# Placa_de_grava_o.net
KiCad netlist of a schematic drawn in Altium Designer
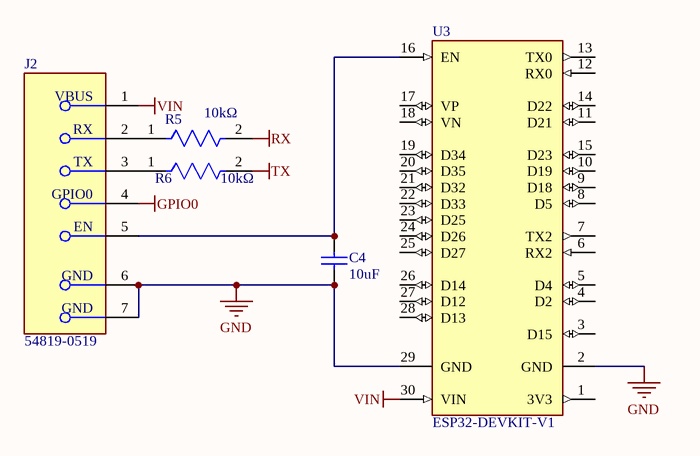
[diagram p0: Placa de gravação.SchDoc]

(export (version "E")
  (design (tool "Eeschema 10.0.6"))
  (components
    (comp (ref "C4")
      (value "10uF")
      (footprint "C_0805")
      (description "Cap Ceramic 1uF 16V X5R 10% SMD 0805 85C Plastic T/R")
      (fields
        (field (name "MANUFACTURER") "KEMET")
        (field (name "MANUFACTURER PART NUMBER") "C0805C105K4PACTU")
      )
      (libsource (lib "uSimar_Components") (part "C0805C105K4PACTU"))
    )
    (comp (ref "J2")
      (value "54819-0519")
      (footprint "FP-54819-0519-MFG")
      (description "CONN RCPT USB2.0 MINI B 5P R/A")
      (libsource (lib "uSimar_Components") (part "CMP-04767-000009-1"))
    )
    (comp (ref "R5")
      (value "10kΩ")
      (footprint "FP-CRCW0805-e3-IPC_C")
      (description "RES Thick Film, 10kΩ, 1%, 0.125W, 100ppm/°C, 0805")
      (fields (field (name "TOLERANCE") "1%"))
      (libsource (lib "uSimar_Components") (part "CMP-2001-04908-2"))
    )
    (comp (ref "R6")
      (value "10kΩ")
      (footprint "FP-CRCW0805-e3-IPC_C")
      (description "RES Thick Film, 10kΩ, 1%, 0.125W, 100ppm/°C, 0805")
      (fields (field (name "TOLERANCE") "1%"))
      (libsource (lib "uSimar_Components") (part "CMP-2001-04908-2"))
    )
    (comp (ref "U3")
      (value "ESP32-DEVKIT-V1")
      (footprint "MODULE_ESP32_DEVKIT_V1")
      (fields (field (name "MF") "Do it"))
      (libsource (lib "uSimar_Components") (part "ESP32-DEVKIT-V1"))
    )
  )
  (nets
    (net (code "1") (name "GND") (class "Default")
      (node (ref "C4") (pin "1") (pinfunction "1_1") (pintype "passive"))
      (node (ref "J2") (pin "6") (pinfunction "MNT_1_6") (pintype "passive"))
      (node (ref "J2") (pin "7") (pinfunction "MNT_2_7") (pintype "passive"))
      (node (ref "U3") (pin "2") (pinfunction "GND_2") (pintype "power_in"))
      (node (ref "U3") (pin "29") (pinfunction "GND_29") (pintype "power_in"))
    )
    (net (code "2") (name "GPIO0") (class "Default")
      (node (ref "J2") (pin "4") (pinfunction "ID_4") (pintype "passive"))
    )
    (net (code "3") (name "Net-(J2-D+)") (class "Default")
      (node (ref "J2") (pin "3") (pinfunction "D+_3") (pintype "passive"))
      (node (ref "R6") (pin "1") (pinfunction "1_1") (pintype "passive"))
    )
    (net (code "4") (name "Net-(J2-GND)") (class "Default")
      (node (ref "C4") (pin "2") (pinfunction "2_2") (pintype "passive"))
      (node (ref "J2") (pin "5") (pinfunction "GND_5") (pintype "power_in"))
      (node (ref "U3") (pin "16") (pinfunction "EN_16") (pintype "input"))
    )
    (net (code "5") (name "Net-(J2-RX)") (class "Default")
      (node (ref "J2") (pin "2") (pinfunction "RX_2") (pintype "passive"))
      (node (ref "R5") (pin "1") (pinfunction "1_1") (pintype "passive"))
    )
    (net (code "6") (name "RX") (class "Default")
      (node (ref "R5") (pin "2") (pinfunction "2_2") (pintype "passive"))
    )
    (net (code "7") (name "TX") (class "Default")
      (node (ref "R6") (pin "2") (pinfunction "2_2") (pintype "passive"))
    )
    (net (code "8") (name "VIN") (class "Default")
      (node (ref "J2") (pin "1") (pinfunction "VBUS_1") (pintype "power_in"))
      (node (ref "U3") (pin "30") (pinfunction "VIN_30") (pintype "input"))
    )
    (net (code "9") (name "unconnected-(U3-3V3-Pad1)") (class "Default")
      (node (ref "U3") (pin "1") (pinfunction "3V3_1") (pintype "output"))
    )
    (net (code "10") (name "unconnected-(U3-D2-Pad4)") (class "Default")
      (node (ref "U3") (pin "4") (pinfunction "D2_4") (pintype "bidirectional"))
    )
    (net (code "11") (name "unconnected-(U3-D4-Pad5)") (class "Default")
      (node (ref "U3") (pin "5") (pinfunction "D4_5") (pintype "bidirectional"))
    )
    (net (code "12") (name "unconnected-(U3-D5-Pad8)") (class "Default")
      (node (ref "U3") (pin "8") (pinfunction "D5_8") (pintype "bidirectional"))
    )
    (net (code "13") (name "unconnected-(U3-D12-Pad27)") (class "Default")
      (node (ref "U3") (pin "27") (pinfunction "D12_27") (pintype "bidirectional"))
    )
    (net (code "14") (name "unconnected-(U3-D13-Pad28)") (class "Default")
      (node (ref "U3") (pin "28") (pinfunction "D13_28") (pintype "bidirectional"))
    )
    (net (code "15") (name "unconnected-(U3-D14-Pad26)") (class "Default")
      (node (ref "U3") (pin "26") (pinfunction "D14_26") (pintype "bidirectional"))
    )
    (net (code "16") (name "unconnected-(U3-D15-Pad3)") (class "Default")
      (node (ref "U3") (pin "3") (pinfunction "D15_3") (pintype "bidirectional"))
    )
    (net (code "17") (name "unconnected-(U3-D18-Pad9)") (class "Default")
      (node (ref "U3") (pin "9") (pinfunction "D18_9") (pintype "bidirectional"))
    )
    (net (code "18") (name "unconnected-(U3-D19-Pad10)") (class "Default")
      (node (ref "U3") (pin "10") (pinfunction "D19_10") (pintype "bidirectional"))
    )
    (net (code "19") (name "unconnected-(U3-D21-Pad11)") (class "Default")
      (node (ref "U3") (pin "11") (pinfunction "D21_11") (pintype "bidirectional"))
    )
    (net (code "20") (name "unconnected-(U3-D22-Pad14)") (class "Default")
      (node (ref "U3") (pin "14") (pinfunction "D22_14") (pintype "bidirectional"))
    )
    (net (code "21") (name "unconnected-(U3-D23-Pad15)") (class "Default")
      (node (ref "U3") (pin "15") (pinfunction "D23_15") (pintype "bidirectional"))
    )
    (net (code "22") (name "unconnected-(U3-D25-Pad23)") (class "Default")
      (node (ref "U3") (pin "23") (pinfunction "D25_23") (pintype "bidirectional"))
    )
    (net (code "23") (name "unconnected-(U3-D26-Pad24)") (class "Default")
      (node (ref "U3") (pin "24") (pinfunction "D26_24") (pintype "bidirectional"))
    )
    (net (code "24") (name "unconnected-(U3-D27-Pad25)") (class "Default")
      (node (ref "U3") (pin "25") (pinfunction "D27_25") (pintype "bidirectional"))
    )
    (net (code "25") (name "unconnected-(U3-D32-Pad21)") (class "Default")
      (node (ref "U3") (pin "21") (pinfunction "D32_21") (pintype "bidirectional"))
    )
    (net (code "26") (name "unconnected-(U3-D33-Pad22)") (class "Default")
      (node (ref "U3") (pin "22") (pinfunction "D33_22") (pintype "bidirectional"))
    )
    (net (code "27") (name "unconnected-(U3-D34-Pad19)") (class "Default")
      (node (ref "U3") (pin "19") (pinfunction "D34_19") (pintype "bidirectional"))
    )
    (net (code "28") (name "unconnected-(U3-D35-Pad20)") (class "Default")
      (node (ref "U3") (pin "20") (pinfunction "D35_20") (pintype "bidirectional"))
    )
    (net (code "29") (name "unconnected-(U3-RX0-Pad12)") (class "Default")
      (node (ref "U3") (pin "12") (pinfunction "RX0_12") (pintype "input"))
    )
    (net (code "30") (name "unconnected-(U3-RX2-Pad6)") (class "Default")
      (node (ref "U3") (pin "6") (pinfunction "RX2_6") (pintype "input"))
    )
    (net (code "31") (name "unconnected-(U3-TX0-Pad13)") (class "Default")
      (node (ref "U3") (pin "13") (pinfunction "TX0_13") (pintype "output"))
    )
    (net (code "32") (name "unconnected-(U3-TX2-Pad7)") (class "Default")
      (node (ref "U3") (pin "7") (pinfunction "TX2_7") (pintype "output"))
    )
    (net (code "33") (name "unconnected-(U3-VN-Pad18)") (class "Default")
      (node (ref "U3") (pin "18") (pinfunction "VN_18") (pintype "bidirectional"))
    )
    (net (code "34") (name "unconnected-(U3-VP-Pad17)") (class "Default")
      (node (ref "U3") (pin "17") (pinfunction "VP_17") (pintype "bidirectional"))
    )
  )
)
